# Teensy3_based_M_M_board_no_routing.net
KiCad netlist of a schematic drawn in EAGLE
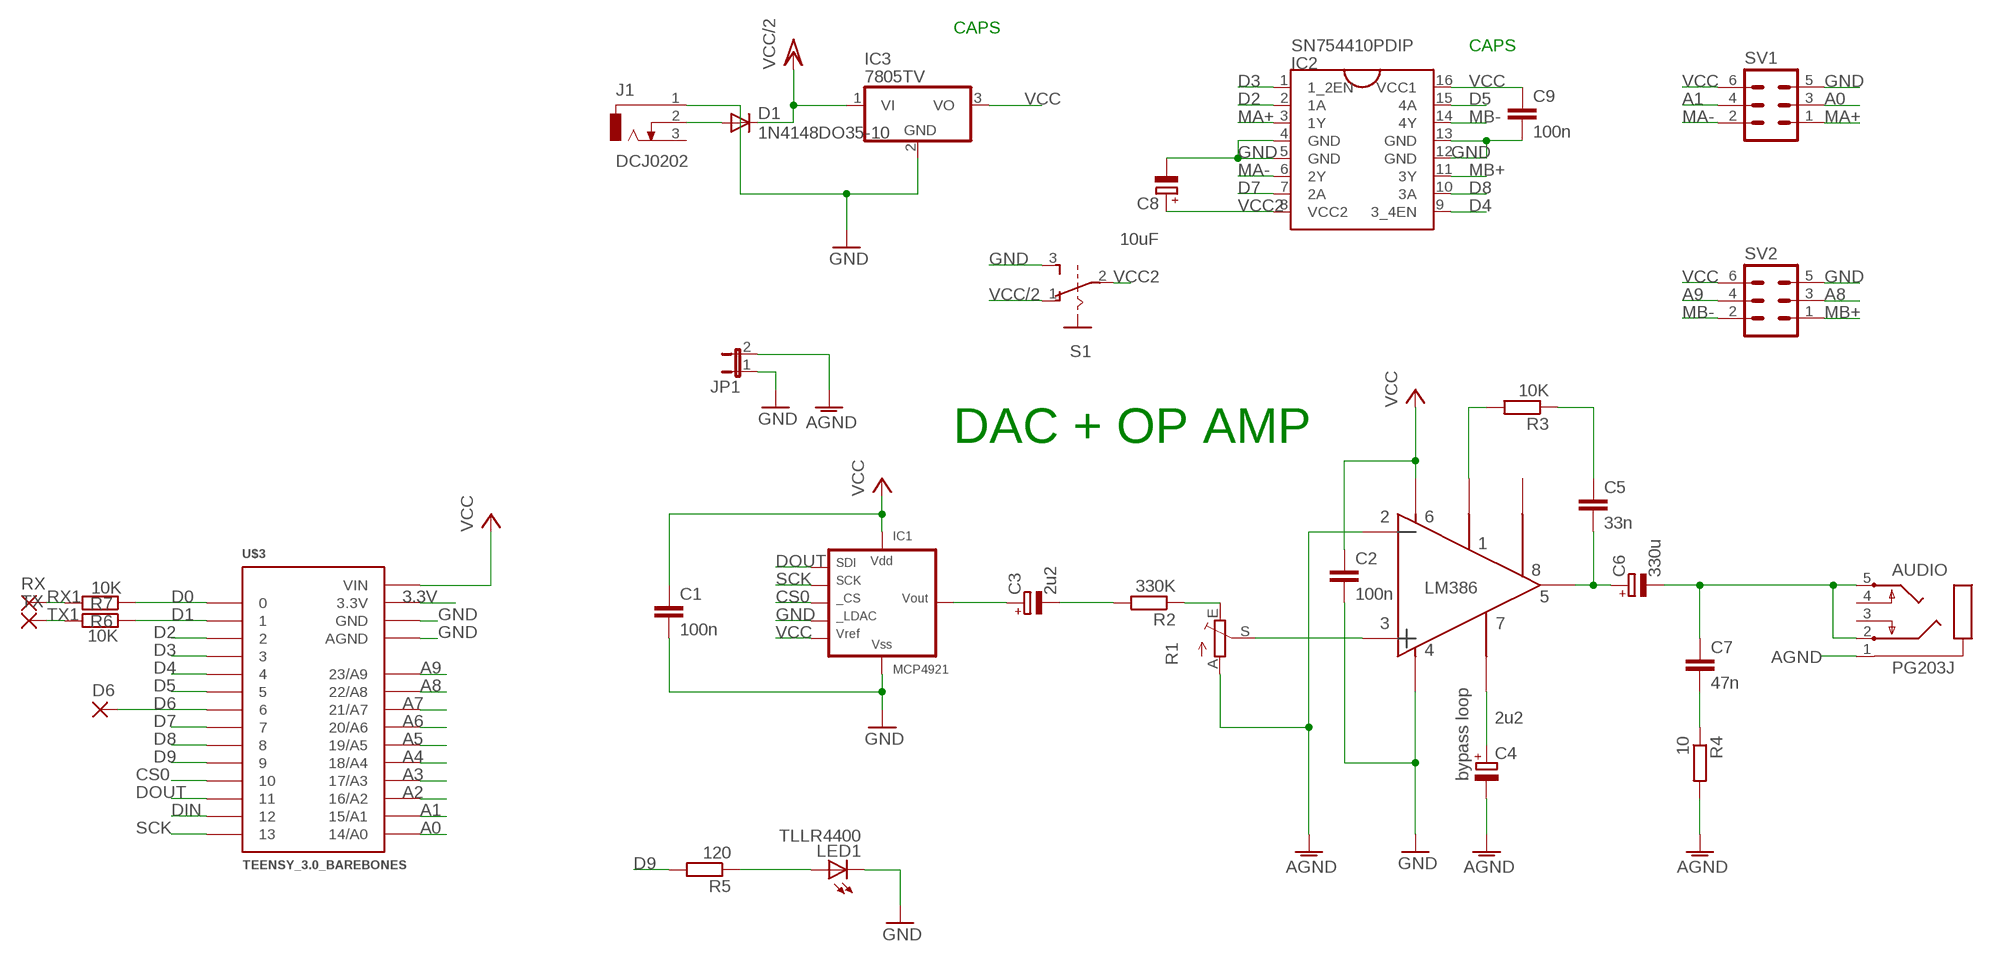
[diagram p0: schematic, sheet 1]

(export (version "E")
  (design (tool "Eeschema 10.0.6"))
  (components
    (comp (ref "AUDIO")
      (value "PG203J")
      (footprint "eagle-import:PG203J")
      (libsource (lib "eagle-import") (part "PG203J"))
    )
    (comp (ref "C1")
      (value "100n")
      (footprint "eagle-import:C050-030X075")
      (libsource (lib "eagle-import") (part "C-EU050-030X075"))
    )
    (comp (ref "C2")
      (value "100n")
      (footprint "eagle-import:C050-030X075")
      (libsource (lib "eagle-import") (part "C-EU050-030X075"))
    )
    (comp (ref "C3")
      (value "2u2")
      (footprint "eagle-import:E2-5")
      (libsource (lib "eagle-import") (part "CPOL-EUE2-5"))
    )
    (comp (ref "C4")
      (value "2u2")
      (footprint "eagle-import:E2-5")
      (libsource (lib "eagle-import") (part "CPOL-EUE2-5"))
    )
    (comp (ref "C5")
      (value "33n")
      (footprint "eagle-import:C050-030X075")
      (libsource (lib "eagle-import") (part "C-EU050-030X075"))
    )
    (comp (ref "C6")
      (value "330u")
      (footprint "eagle-import:E2,5-7")
      (libsource (lib "eagle-import") (part "CPOL-EUE2.5-7"))
    )
    (comp (ref "C7")
      (value "47n")
      (footprint "eagle-import:C050-030X075")
      (libsource (lib "eagle-import") (part "C-EU050-030X075"))
    )
    (comp (ref "C8")
      (value "10uF")
      (footprint "eagle-import:E2-5")
      (libsource (lib "eagle-import") (part "CPOL-EUE2-5"))
    )
    (comp (ref "C9")
      (value "100n")
      (footprint "eagle-import:C050-030X075")
      (libsource (lib "eagle-import") (part "C-EU050-030X075"))
    )
    (comp (ref "D1")
      (value "1N4148DO35-10")
      (footprint "eagle-import:DO35-10")
      (libsource (lib "eagle-import") (part "1N4148DO35-10"))
    )
    (comp (ref "D6")
      (value "2,15/1,0")
      (footprint "eagle-import:2,15_1,0")
      (libsource (lib "eagle-import") (part "2,15/1,0"))
    )
    (comp (ref "IC1")
      (value "MCP4921")
      (footprint "eagle-import:DIL8")
      (libsource (lib "eagle-import") (part "MCP4921P"))
    )
    (comp (ref "IC2")
      (value "SN754410PDIP")
      (footprint "eagle-import:DIL16")
      (libsource (lib "eagle-import") (part "SN754410PDIP"))
    )
    (comp (ref "IC3")
      (value "7805TV")
      (footprint "eagle-import:TO220V")
      (libsource (lib "eagle-import") (part "78TV05"))
    )
    (comp (ref "J1")
      (value "DCJ0202")
      (footprint "eagle-import:DCJ0202")
      (libsource (lib "eagle-import") (part "DCJ0202"))
    )
    (comp (ref "JP1")
      (value "JP1E")
      (footprint "eagle-import:JP1")
      (libsource (lib "eagle-import") (part "JP1E"))
    )
    (comp (ref "LED1")
      (value "TLLR4400")
      (footprint "eagle-import:LED3MM")
      (fields (field (name "MF") "VISHAY SEMICONDUCTOR"))
      (libsource (lib "eagle-import") (part "TLLR4400"))
    )
    (comp (ref "R1")
      (value "TRIM_EU-CA9V")
      (footprint "eagle-import:CA9V")
      (libsource (lib "eagle-import") (part "TRIM_EU-CA9V"))
    )
    (comp (ref "R2")
      (value "330K")
      (footprint "eagle-import:0207_10")
      (libsource (lib "eagle-import") (part "R-EU_0207/10"))
    )
    (comp (ref "R3")
      (value "10K")
      (footprint "eagle-import:0207_10")
      (libsource (lib "eagle-import") (part "R-EU_0207/10"))
    )
    (comp (ref "R4")
      (value "10")
      (footprint "eagle-import:0207_10")
      (libsource (lib "eagle-import") (part "R-EU_0207/10"))
    )
    (comp (ref "R5")
      (value "120")
      (footprint "eagle-import:0207_10")
      (libsource (lib "eagle-import") (part "R-EU_0207/10"))
    )
    (comp (ref "R6")
      (value "10K")
      (footprint "eagle-import:0207_10")
      (libsource (lib "eagle-import") (part "R-EU_0207/10"))
    )
    (comp (ref "R7")
      (value "10K")
      (footprint "eagle-import:0207_10")
      (libsource (lib "eagle-import") (part "R-EU_0207/10"))
    )
    (comp (ref "RX")
      (value "2,15/1,0")
      (footprint "eagle-import:2,15_1,0")
      (libsource (lib "eagle-import") (part "2,15/1,0"))
    )
    (comp (ref "S1")
      (value "EG1218")
      (footprint "eagle-import:GF-126-0159")
      (libsource (lib "eagle-import") (part "EG1218"))
    )
    (comp (ref "SV1")
      (value "ML6")
      (footprint "eagle-import:ML6")
      (libsource (lib "eagle-import") (part "ML6"))
    )
    (comp (ref "SV2")
      (value "ML6")
      (footprint "eagle-import:ML6")
      (libsource (lib "eagle-import") (part "ML6"))
    )
    (comp (ref "TX")
      (value "2,15/1,0")
      (footprint "eagle-import:2,15_1,0")
      (libsource (lib "eagle-import") (part "2,15/1,0"))
    )
    (comp (ref "U$2")
      (value "LM386")
      (footprint "eagle-import:LM386")
      (libsource (lib "eagle-import") (part "LM386OA"))
    )
    (comp (ref "U$3")
      (value "TEENSY_3.0_BAREBONES")
      (footprint "eagle-import:TEENSY_3.0_BAREBONES")
      (libsource (lib "eagle-import") (part "TEENSY_3.0_BAREBONES"))
    )
  )
  (nets
    (net (code "1") (name "/3.3V") (class "Default")
      (node (ref "U$3") (pin "3.3V") (pinfunction "3.3V_3.3V") (pintype "power_in"))
    )
    (net (code "2") (name "/A0") (class "Default")
      (node (ref "SV1") (pin "3") (pinfunction "3_3") (pintype "passive"))
      (node (ref "U$3") (pin "14/A0") (pinfunction "14/A0_14/A0") (pintype "bidirectional"))
    )
    (net (code "3") (name "/A1") (class "Default")
      (node (ref "SV1") (pin "4") (pinfunction "4_4") (pintype "passive"))
      (node (ref "U$3") (pin "15/A1") (pinfunction "15/A1_15/A1") (pintype "bidirectional"))
    )
    (net (code "4") (name "/A2") (class "Default")
      (node (ref "U$3") (pin "16/A2") (pinfunction "16/A2_16/A2") (pintype "bidirectional"))
    )
    (net (code "5") (name "/A3") (class "Default")
      (node (ref "U$3") (pin "17/A3") (pinfunction "17/A3_17/A3") (pintype "bidirectional"))
    )
    (net (code "6") (name "/A4") (class "Default")
      (node (ref "U$3") (pin "18/A4") (pinfunction "18/A4_18/A4") (pintype "bidirectional"))
    )
    (net (code "7") (name "/A5") (class "Default")
      (node (ref "U$3") (pin "19/A5") (pinfunction "19/A5_19/A5") (pintype "bidirectional"))
    )
    (net (code "8") (name "/A6") (class "Default")
      (node (ref "U$3") (pin "20/A6") (pinfunction "20/A6_20/A6") (pintype "bidirectional"))
    )
    (net (code "9") (name "/A7") (class "Default")
      (node (ref "U$3") (pin "21/A7") (pinfunction "21/A7_21/A7") (pintype "bidirectional"))
    )
    (net (code "10") (name "/A8") (class "Default")
      (node (ref "SV2") (pin "3") (pinfunction "3_3") (pintype "passive"))
      (node (ref "U$3") (pin "22/A8") (pinfunction "22/A8_22/A8") (pintype "bidirectional"))
    )
    (net (code "11") (name "/A9") (class "Default")
      (node (ref "SV2") (pin "4") (pinfunction "4_4") (pintype "passive"))
      (node (ref "U$3") (pin "23/A9") (pinfunction "23/A9_23/A9") (pintype "bidirectional"))
    )
    (net (code "12") (name "/CS0") (class "Default")
      (node (ref "IC1") (pin "2") (pinfunction "CS_2") (pintype "input"))
      (node (ref "U$3") (pin "10") (pinfunction "10_10") (pintype "bidirectional"))
    )
    (net (code "13") (name "/D0") (class "Default")
      (node (ref "R7") (pin "1") (pinfunction "1_1") (pintype "passive"))
      (node (ref "U$3") (pin "0") (pinfunction "0_0") (pintype "bidirectional"))
    )
    (net (code "14") (name "/D1") (class "Default")
      (node (ref "R6") (pin "1") (pinfunction "1_1") (pintype "passive"))
      (node (ref "U$3") (pin "1") (pinfunction "1_1") (pintype "bidirectional"))
    )
    (net (code "15") (name "/D2") (class "Default")
      (node (ref "IC2") (pin "2") (pinfunction "1A_2") (pintype "bidirectional"))
      (node (ref "U$3") (pin "2") (pinfunction "2_2") (pintype "bidirectional"))
    )
    (net (code "16") (name "/D3") (class "Default")
      (node (ref "IC2") (pin "1") (pinfunction "1_2EN_1") (pintype "bidirectional"))
      (node (ref "U$3") (pin "3") (pinfunction "3_3") (pintype "bidirectional"))
    )
    (net (code "17") (name "/D4") (class "Default")
      (node (ref "IC2") (pin "9") (pinfunction "3_4EN_9") (pintype "bidirectional"))
      (node (ref "U$3") (pin "4") (pinfunction "4_4") (pintype "bidirectional"))
    )
    (net (code "18") (name "/D5") (class "Default")
      (node (ref "IC2") (pin "15") (pinfunction "4A_15") (pintype "bidirectional"))
      (node (ref "U$3") (pin "5") (pinfunction "5_5") (pintype "bidirectional"))
    )
    (net (code "19") (name "/D6") (class "Default")
      (node (ref "D6") (pin "1") (pinfunction "P_1") (pintype "passive"))
      (node (ref "U$3") (pin "6") (pinfunction "6_6") (pintype "bidirectional"))
    )
    (net (code "20") (name "/D7") (class "Default")
      (node (ref "IC2") (pin "7") (pinfunction "2A_7") (pintype "bidirectional"))
      (node (ref "U$3") (pin "7") (pinfunction "7_7") (pintype "bidirectional"))
    )
    (net (code "21") (name "/D8") (class "Default")
      (node (ref "IC2") (pin "10") (pinfunction "3A_10") (pintype "bidirectional"))
      (node (ref "U$3") (pin "8") (pinfunction "8_8") (pintype "bidirectional"))
    )
    (net (code "22") (name "/D9") (class "Default")
      (node (ref "R5") (pin "2") (pinfunction "2_2") (pintype "passive"))
      (node (ref "U$3") (pin "9") (pinfunction "9_9") (pintype "bidirectional"))
    )
    (net (code "23") (name "/DIN") (class "Default")
      (node (ref "U$3") (pin "12") (pinfunction "12_12") (pintype "bidirectional"))
    )
    (net (code "24") (name "/DOUT") (class "Default")
      (node (ref "IC1") (pin "4") (pinfunction "SDI_4") (pintype "input"))
      (node (ref "U$3") (pin "11") (pinfunction "11_11") (pintype "bidirectional"))
    )
    (net (code "25") (name "/MA+") (class "Default")
      (node (ref "IC2") (pin "3") (pinfunction "1Y_3") (pintype "bidirectional"))
      (node (ref "SV1") (pin "1") (pinfunction "1_1") (pintype "passive"))
    )
    (net (code "26") (name "/MA-") (class "Default")
      (node (ref "IC2") (pin "6") (pinfunction "2Y_6") (pintype "bidirectional"))
      (node (ref "SV1") (pin "2") (pinfunction "2_2") (pintype "passive"))
    )
    (net (code "27") (name "/MB+") (class "Default")
      (node (ref "IC2") (pin "11") (pinfunction "3Y_11") (pintype "bidirectional"))
      (node (ref "SV2") (pin "1") (pinfunction "1_1") (pintype "passive"))
    )
    (net (code "28") (name "/MB-") (class "Default")
      (node (ref "IC2") (pin "14") (pinfunction "4Y_14") (pintype "bidirectional"))
      (node (ref "SV2") (pin "2") (pinfunction "2_2") (pintype "passive"))
    )
    (net (code "29") (name "/RX1") (class "Default")
      (node (ref "R7") (pin "2") (pinfunction "2_2") (pintype "passive"))
      (node (ref "RX") (pin "1") (pinfunction "P_1") (pintype "passive"))
    )
    (net (code "30") (name "/SCK") (class "Default")
      (node (ref "IC1") (pin "3") (pinfunction "SCK_3") (pintype "input"))
      (node (ref "U$3") (pin "13") (pinfunction "13_13") (pintype "bidirectional"))
    )
    (net (code "31") (name "/TX1") (class "Default")
      (node (ref "R6") (pin "2") (pinfunction "2_2") (pintype "passive"))
      (node (ref "TX") (pin "1") (pinfunction "P_1") (pintype "passive"))
    )
    (net (code "32") (name "/VCC2") (class "Default")
      (node (ref "C8") (pin "+") (pinfunction "+_+") (pintype "passive"))
      (node (ref "IC2") (pin "8") (pinfunction "VCC2_8") (pintype "bidirectional"))
      (node (ref "S1") (pin "2") (pinfunction "02_2") (pintype "passive"))
    )
    (net (code "33") (name "AGND") (class "Default")
      (node (ref "AUDIO") (pin "1") (pinfunction "1_1") (pintype "passive"))
      (node (ref "C4") (pin "-") (pinfunction "-_-") (pintype "passive"))
      (node (ref "JP1") (pin "2") (pinfunction "2_2") (pintype "passive"))
      (node (ref "R1") (pin "A") (pinfunction "A_A") (pintype "passive"))
      (node (ref "R4") (pin "2") (pinfunction "2_2") (pintype "passive"))
      (node (ref "U$2") (pin "2") (pinfunction "P$2_2") (pintype "bidirectional"))
    )
    (net (code "34") (name "GND") (class "Default")
      (node (ref "C1") (pin "2") (pinfunction "2_2") (pintype "passive"))
      (node (ref "C2") (pin "2") (pinfunction "2_2") (pintype "passive"))
      (node (ref "C8") (pin "-") (pinfunction "-_-") (pintype "passive"))
      (node (ref "C9") (pin "2") (pinfunction "2_2") (pintype "passive"))
      (node (ref "IC1") (pin "5") (pinfunction "LDAC_5") (pintype "input"))
      (node (ref "IC1") (pin "7") (pinfunction "VSS_7") (pintype "power_in"))
      (node (ref "IC2") (pin "12") (pinfunction "GND_12") (pintype "bidirectional"))
      (node (ref "IC2") (pin "13") (pinfunction "GND_13") (pintype "bidirectional"))
      (node (ref "IC2") (pin "4") (pinfunction "GND_4") (pintype "bidirectional"))
      (node (ref "IC2") (pin "5") (pinfunction "GND_5") (pintype "bidirectional"))
      (node (ref "IC3") (pin "2") (pinfunction "GND_2") (pintype "passive"))
      (node (ref "J1") (pin "1") (pinfunction "1_1") (pintype "passive"))
      (node (ref "JP1") (pin "1") (pinfunction "1_1") (pintype "passive"))
      (node (ref "LED1") (pin "K") (pinfunction "C_K") (pintype "passive"))
      (node (ref "S1") (pin "3") (pinfunction "3_3") (pintype "passive"))
      (node (ref "SV1") (pin "5") (pinfunction "5_5") (pintype "passive"))
      (node (ref "SV2") (pin "5") (pinfunction "5_5") (pintype "passive"))
      (node (ref "U$2") (pin "4") (pinfunction "P$4_4") (pintype "bidirectional"))
      (node (ref "U$3") (pin "AGND") (pinfunction "AGND_AGND") (pintype "power_in"))
      (node (ref "U$3") (pin "GND") (pinfunction "GND_GND") (pintype "power_in"))
    )
    (net (code "35") (name "Net-(AUDIO-Pad2)") (class "Default")
      (node (ref "AUDIO") (pin "2") (pinfunction "2_2") (pintype "passive"))
      (node (ref "AUDIO") (pin "5") (pinfunction "5_5") (pintype "passive"))
      (node (ref "C6") (pin "-") (pinfunction "-_-") (pintype "passive"))
      (node (ref "C7") (pin "1") (pinfunction "1_1") (pintype "passive"))
    )
    (net (code "36") (name "Net-(C3-Pad-)") (class "Default")
      (node (ref "C3") (pin "-") (pinfunction "-_-") (pintype "passive"))
      (node (ref "R2") (pin "2") (pinfunction "2_2") (pintype "passive"))
    )
    (net (code "37") (name "Net-(C5-Pad1)") (class "Default")
      (node (ref "C5") (pin "1") (pinfunction "1_1") (pintype "passive"))
      (node (ref "R3") (pin "1") (pinfunction "1_1") (pintype "passive"))
    )
    (net (code "38") (name "Net-(C7-Pad2)") (class "Default")
      (node (ref "C7") (pin "2") (pinfunction "2_2") (pintype "passive"))
      (node (ref "R4") (pin "1") (pinfunction "1_1") (pintype "passive"))
    )
    (net (code "39") (name "Net-(D1-PadA)") (class "Default")
      (node (ref "D1") (pin "A") (pinfunction "A_A") (pintype "passive"))
      (node (ref "J1") (pin "2") (pinfunction "2_2") (pintype "passive"))
    )
    (net (code "40") (name "Net-(IC1-VOUT)") (class "Default")
      (node (ref "C3") (pin "+") (pinfunction "+_+") (pintype "passive"))
      (node (ref "IC1") (pin "8") (pinfunction "VOUT_8") (pintype "output"))
    )
    (net (code "41") (name "Net-(LED1-PadA)") (class "Default")
      (node (ref "LED1") (pin "A") (pinfunction "A_A") (pintype "passive"))
      (node (ref "R5") (pin "1") (pinfunction "1_1") (pintype "passive"))
    )
    (net (code "42") (name "Net-(R1-PadE)") (class "Default")
      (node (ref "R1") (pin "E") (pinfunction "E_E") (pintype "passive"))
      (node (ref "R2") (pin "1") (pinfunction "1_1") (pintype "passive"))
    )
    (net (code "43") (name "Net-(U$2-P$1)") (class "Default")
      (node (ref "R3") (pin "2") (pinfunction "2_2") (pintype "passive"))
      (node (ref "U$2") (pin "1") (pinfunction "P$1_1") (pintype "bidirectional"))
    )
    (net (code "44") (name "Net-(U$2-P$3)") (class "Default")
      (node (ref "R1") (pin "S") (pinfunction "S_S") (pintype "passive"))
      (node (ref "U$2") (pin "3") (pinfunction "P$3_3") (pintype "bidirectional"))
    )
    (net (code "45") (name "Net-(U$2-P$5)") (class "Default")
      (node (ref "C5") (pin "2") (pinfunction "2_2") (pintype "passive"))
      (node (ref "C6") (pin "+") (pinfunction "+_+") (pintype "passive"))
      (node (ref "U$2") (pin "5") (pinfunction "P$5_5") (pintype "bidirectional"))
    )
    (net (code "46") (name "Net-(U$2-P$7)") (class "Default")
      (node (ref "C4") (pin "+") (pinfunction "+_+") (pintype "passive"))
      (node (ref "U$2") (pin "7") (pinfunction "P$7_7") (pintype "bidirectional"))
    )
    (net (code "47") (name "VCC") (class "Default")
      (node (ref "C1") (pin "1") (pinfunction "1_1") (pintype "passive"))
      (node (ref "C2") (pin "1") (pinfunction "1_1") (pintype "passive"))
      (node (ref "C9") (pin "1") (pinfunction "1_1") (pintype "passive"))
      (node (ref "IC1") (pin "1") (pinfunction "VDD_1") (pintype "power_in"))
      (node (ref "IC1") (pin "6") (pinfunction "VREF_6") (pintype "input"))
      (node (ref "IC2") (pin "16") (pinfunction "VCC1_16") (pintype "bidirectional"))
      (node (ref "IC3") (pin "3") (pinfunction "VO_3") (pintype "passive"))
      (node (ref "SV1") (pin "6") (pinfunction "6_6") (pintype "passive"))
      (node (ref "SV2") (pin "6") (pinfunction "6_6") (pintype "passive"))
      (node (ref "U$2") (pin "6") (pinfunction "P$6_6") (pintype "bidirectional"))
      (node (ref "U$3") (pin "VIN") (pinfunction "VIN_VIN") (pintype "power_in"))
    )
    (net (code "48") (name "VCC{slash}2") (class "Default")
      (node (ref "D1") (pin "C") (pinfunction "C_C") (pintype "passive"))
      (node (ref "IC3") (pin "1") (pinfunction "VI_1") (pintype "input"))
      (node (ref "S1") (pin "1") (pinfunction "1_1") (pintype "passive"))
    )
    (net (code "49") (name "unconnected-(AUDIO-Pad3)") (class "Default")
      (node (ref "AUDIO") (pin "3") (pinfunction "3_3") (pintype "passive"))
    )
    (net (code "50") (name "unconnected-(AUDIO-Pad4)") (class "Default")
      (node (ref "AUDIO") (pin "4") (pinfunction "4_4") (pintype "passive"))
    )
    (net (code "51") (name "unconnected-(J1-Pad3)") (class "Default")
      (node (ref "J1") (pin "3") (pinfunction "3_3") (pintype "passive"))
    )
    (net (code "52") (name "unconnected-(U$2-P$8-Pad8)") (class "Default")
      (node (ref "U$2") (pin "8") (pinfunction "P$8_8") (pintype "bidirectional"))
    )
  )
)
